# Sheet_4_2025-09-09.net
KiCad netlist of a schematic drawn in Altium Designer
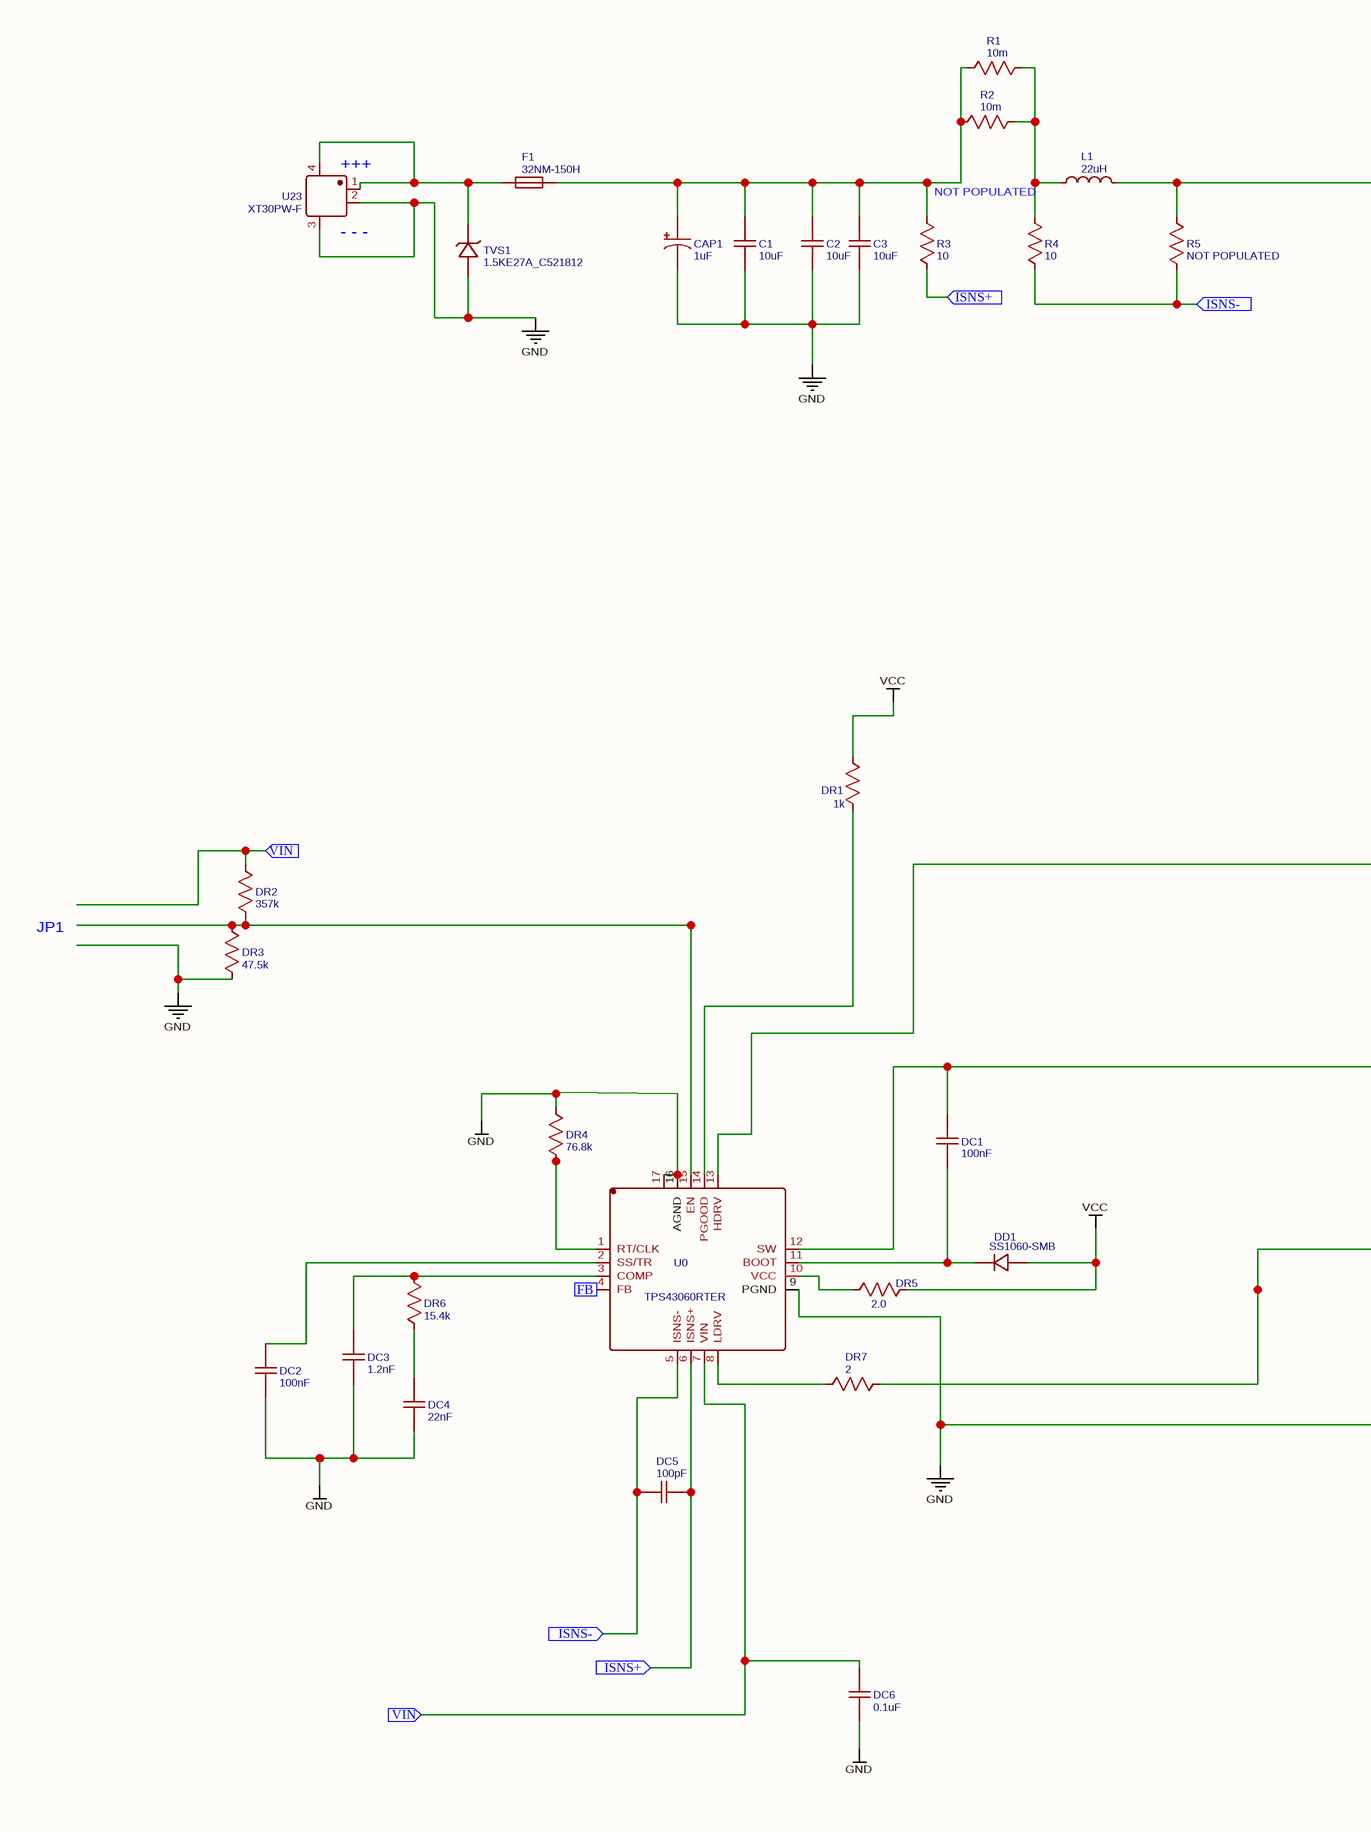
[diagram p0: Sheet_4_2025-09-09.schdoc, left]
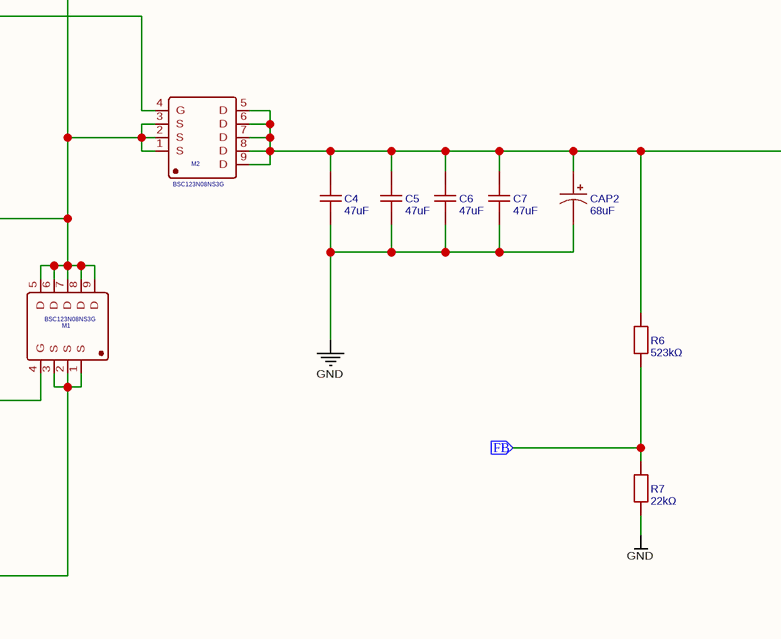
[diagram p1: Sheet_4_2025-09-09.schdoc, middle]
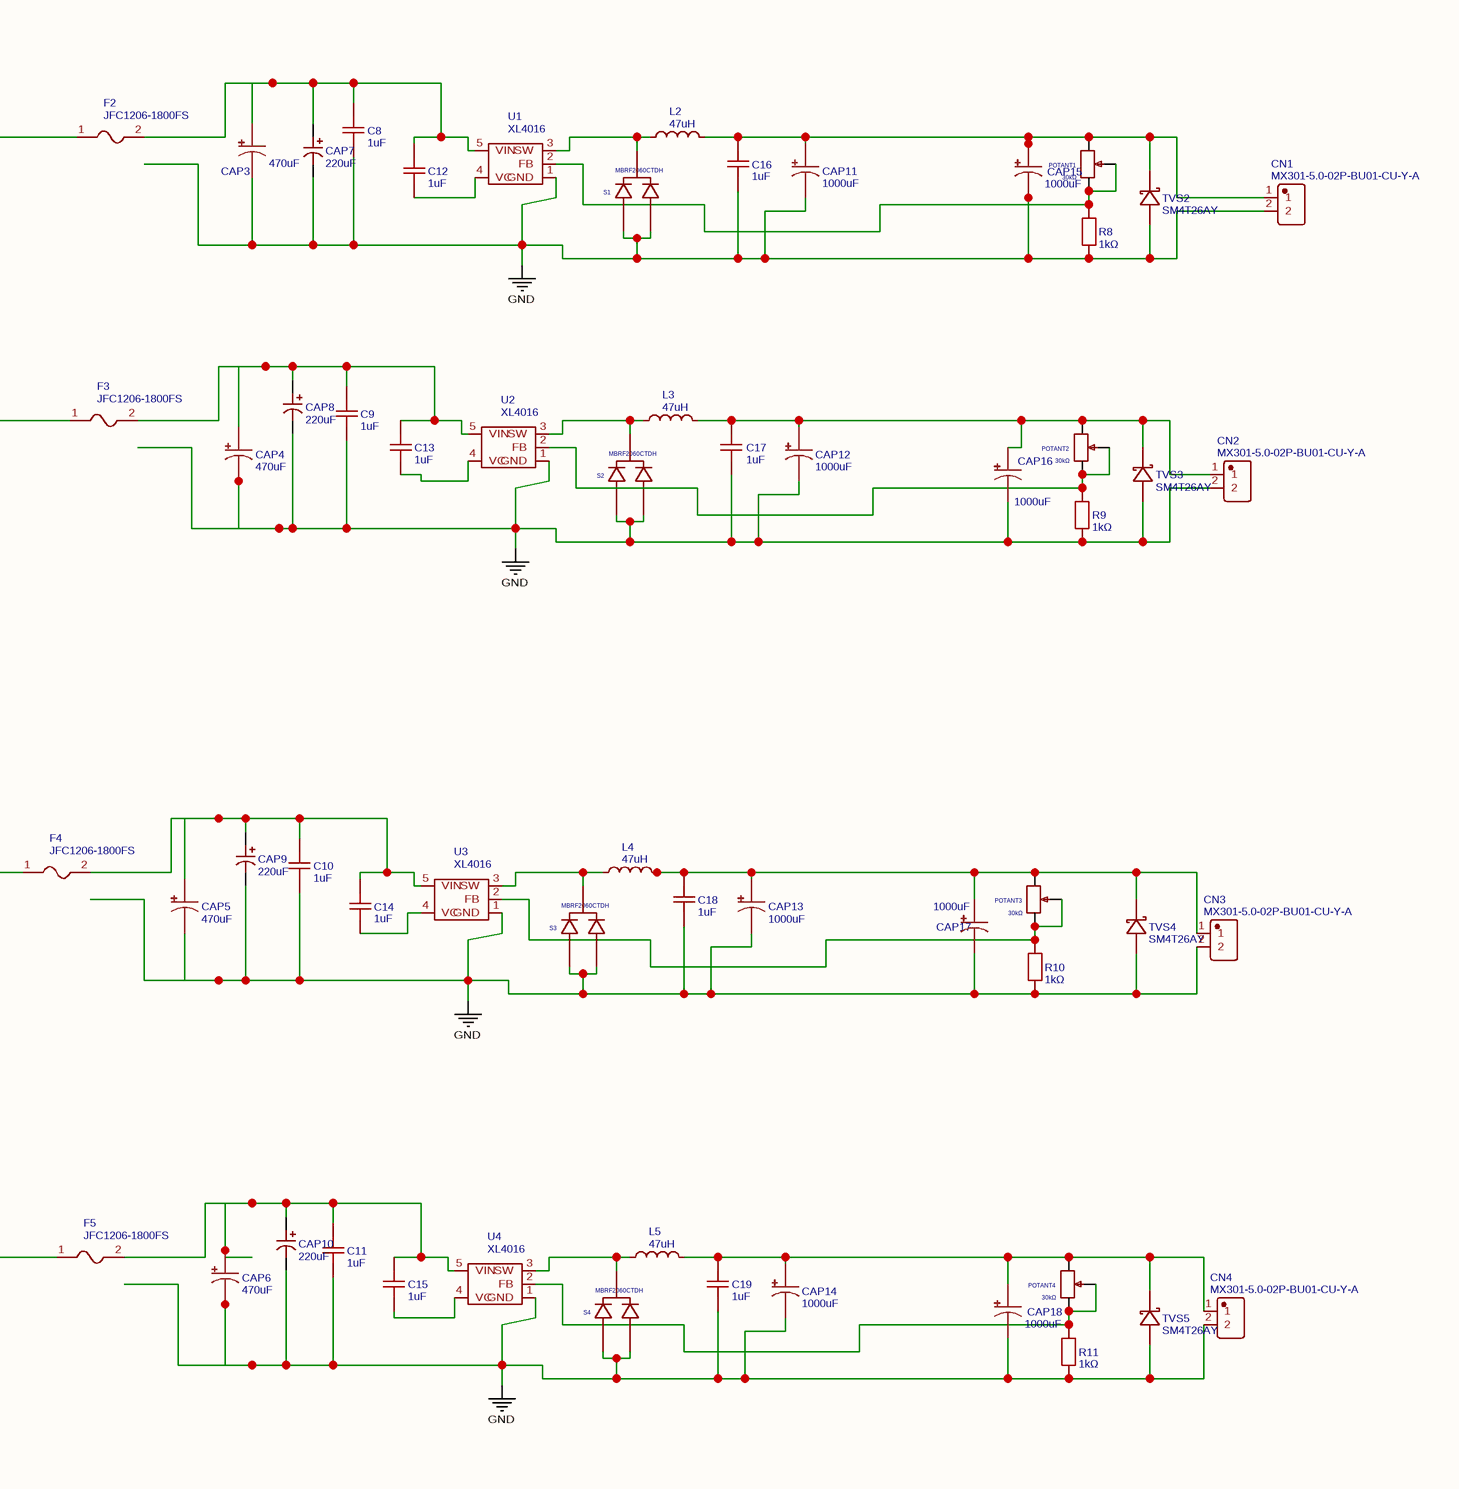
[diagram p2: Sheet_4_2025-09-09.schdoc, right]

(export (version "E")
  (design (tool "Eeschema 10.0.6"))
  (components
    (comp (ref "C1")
      (value "10uF")
      (fields
        (field (name "MANUFACTURER") "TDK")
        (field (name "MANUFACTURER PART") "CNC6P1X7R1H106K250AE")
        (field (name "CONTRIBUTOR") "lcsc")
      )
      (libsource (lib "altium-import") (part "root_3_10uF_"))
    )
    (comp (ref "C2")
      (value "10uF")
      (fields
        (field (name "MANUFACTURER") "TDK")
        (field (name "MANUFACTURER PART") "CNC6P1X7R1H106K250AE")
        (field (name "CONTRIBUTOR") "lcsc")
      )
      (libsource (lib "altium-import") (part "root_3_10uF_"))
    )
    (comp (ref "C3")
      (value "10uF")
      (fields
        (field (name "MANUFACTURER") "TDK")
        (field (name "MANUFACTURER PART") "CNC6P1X7R1H106K250AE")
        (field (name "CONTRIBUTOR") "lcsc")
      )
      (libsource (lib "altium-import") (part "root_3_10uF_"))
    )
    (comp (ref "C4")
      (value "47uF")
      (fields (field (name "CONTRIBUTOR") "LCEDA_Lib"))
      (libsource (lib "altium-import") (part "root_1_47uF_"))
    )
    (comp (ref "C5")
      (value "47uF")
      (fields (field (name "CONTRIBUTOR") "LCEDA_Lib"))
      (libsource (lib "altium-import") (part "root_1_47uF_"))
    )
    (comp (ref "C6")
      (value "47uF")
      (fields (field (name "CONTRIBUTOR") "LCEDA_Lib"))
      (libsource (lib "altium-import") (part "root_1_47uF_"))
    )
    (comp (ref "C7")
      (value "47uF")
      (fields (field (name "CONTRIBUTOR") "LCEDA_Lib"))
      (libsource (lib "altium-import") (part "root_1_47uF_"))
    )
    (comp (ref "C8")
      (value "1uF")
      (fields
        (field (name "MANUFACTURER") "TDK")
        (field (name "MANUFACTURER PART") "FK26X7R1H105KRE06")
        (field (name "CONTRIBUTOR") "LCSC")
      )
      (libsource (lib "altium-import") (part "root_3_1uF_"))
    )
    (comp (ref "C9")
      (value "1uF")
      (fields
        (field (name "MANUFACTURER") "TDK")
        (field (name "MANUFACTURER PART") "FK26X7R1H105KRE06")
        (field (name "CONTRIBUTOR") "LCSC")
      )
      (libsource (lib "altium-import") (part "root_3_1uF_"))
    )
    (comp (ref "C10")
      (value "1uF")
      (fields
        (field (name "MANUFACTURER") "TDK")
        (field (name "MANUFACTURER PART") "FK26X7R1H105KRE06")
        (field (name "CONTRIBUTOR") "LCSC")
      )
      (libsource (lib "altium-import") (part "root_3_1uF_"))
    )
    (comp (ref "C11")
      (value "1uF")
      (fields
        (field (name "MANUFACTURER") "TDK")
        (field (name "MANUFACTURER PART") "FK26X7R1H105KRE06")
        (field (name "CONTRIBUTOR") "LCSC")
      )
      (libsource (lib "altium-import") (part "root_3_1uF_"))
    )
    (comp (ref "C12")
      (value "1uF")
      (fields
        (field (name "MANUFACTURER") "TDK")
        (field (name "MANUFACTURER PART") "C1005X6S1A105K050BC")
        (field (name "CONTRIBUTOR") "lcsc")
      )
      (libsource (lib "") (part "root_3_1uF__1"))
    )
    (comp (ref "C13")
      (value "1uF")
      (fields
        (field (name "MANUFACTURER") "TDK")
        (field (name "MANUFACTURER PART") "C1005X6S1A105K050BC")
        (field (name "CONTRIBUTOR") "lcsc")
      )
      (libsource (lib "") (part "root_3_1uF__1"))
    )
    (comp (ref "C14")
      (value "1uF")
      (fields
        (field (name "MANUFACTURER") "TDK")
        (field (name "MANUFACTURER PART") "C1005X6S1A105K050BC")
        (field (name "CONTRIBUTOR") "lcsc")
      )
      (libsource (lib "") (part "root_3_1uF__1"))
    )
    (comp (ref "C15")
      (value "1uF")
      (fields
        (field (name "MANUFACTURER") "TDK")
        (field (name "MANUFACTURER PART") "C1005X6S1A105K050BC")
        (field (name "CONTRIBUTOR") "lcsc")
      )
      (libsource (lib "altium-import") (part "root_1_1uF_"))
    )
    (comp (ref "C16")
      (value "1uF")
      (fields
        (field (name "MANUFACTURER") "TDK")
        (field (name "MANUFACTURER PART") "FK26X7R1H105KRE06")
        (field (name "CONTRIBUTOR") "LCSC")
      )
      (libsource (lib "altium-import") (part "root_3_1uF_"))
    )
    (comp (ref "C17")
      (value "1uF")
      (fields
        (field (name "MANUFACTURER") "TDK")
        (field (name "MANUFACTURER PART") "FK26X7R1H105KRE06")
        (field (name "CONTRIBUTOR") "LCSC")
      )
      (libsource (lib "") (part "root_3_1uF__2"))
    )
    (comp (ref "C18")
      (value "1uF")
      (fields
        (field (name "MANUFACTURER") "TDK")
        (field (name "MANUFACTURER PART") "FK26X7R1H105KRE06")
        (field (name "CONTRIBUTOR") "LCSC")
      )
      (libsource (lib "altium-import") (part "root_3_1uF_"))
    )
    (comp (ref "C19")
      (value "1uF")
      (fields
        (field (name "MANUFACTURER") "TDK")
        (field (name "MANUFACTURER PART") "FK26X7R1H105KRE06")
        (field (name "CONTRIBUTOR") "LCSC")
      )
      (libsource (lib "altium-import") (part "root_3_1uF_"))
    )
    (comp (ref "CAP1")
      (value "1uF")
      (fields (field (name "MANUFACTURER") "HONOR(荣誉)") (field (name "MANUFACTURER PART") "HT2A1R0M0405"))
      (libsource (lib "altium-import") (part "root_0_1uF_"))
    )
    (comp (ref "CAP2")
      (value "68uF")
      (fields (field (name "CONTRIBUTOR") "LCEDA_Lib"))
      (libsource (lib "altium-import") (part "root_3_68uF_"))
    )
    (comp (ref "CAP3")
      (value "470uF")
      (fields
        (field (name "MANUFACTURER") "BERYL(绿宝石)")
        (field (name "MANUFACTURER PART") "RC063M471LO13*20TH-2A1E")
        (field (name "CONTRIBUTOR") "LCSC")
      )
      (libsource (lib "altium-import") (part "root_0_470uF_"))
    )
    (comp (ref "CAP4")
      (value "470uF")
      (fields
        (field (name "MANUFACTURER") "BERYL(绿宝石)")
        (field (name "MANUFACTURER PART") "RC063M471LO13*20TH-2A1E")
        (field (name "CONTRIBUTOR") "LCSC")
      )
      (libsource (lib "altium-import") (part "root_0_470uF_"))
    )
    (comp (ref "CAP5")
      (value "470uF")
      (fields
        (field (name "MANUFACTURER") "BERYL(绿宝石)")
        (field (name "MANUFACTURER PART") "RC063M471LO13*20TH-2A1E")
        (field (name "CONTRIBUTOR") "LCSC")
      )
      (libsource (lib "altium-import") (part "root_0_470uF_"))
    )
    (comp (ref "CAP6")
      (value "470uF")
      (fields
        (field (name "MANUFACTURER") "BERYL(绿宝石)")
        (field (name "MANUFACTURER PART") "RC063M471LO13*20TH-2A1E")
        (field (name "CONTRIBUTOR") "LCSC")
      )
      (libsource (lib "altium-import") (part "root_0_470uF_"))
    )
    (comp (ref "CAP7")
      (value "220uF")
      (fields
        (field (name "MANUFACTURER") "KNSCHA(科尼盛)")
        (field (name "MANUFACTURER PART") "189RV0038")
        (field (name "CONTRIBUTOR") "lcsc")
      )
      (libsource (lib "altium-import") (part "root_3_220uF_"))
    )
    (comp (ref "CAP8")
      (value "220uF")
      (fields
        (field (name "MANUFACTURER") "KNSCHA(科尼盛)")
        (field (name "MANUFACTURER PART") "189RV0038")
        (field (name "CONTRIBUTOR") "lcsc")
      )
      (libsource (lib "altium-import") (part "root_3_220uF_"))
    )
    (comp (ref "CAP9")
      (value "220uF")
      (fields
        (field (name "MANUFACTURER") "KNSCHA(科尼盛)")
        (field (name "MANUFACTURER PART") "189RV0038")
        (field (name "CONTRIBUTOR") "lcsc")
      )
      (libsource (lib "altium-import") (part "root_3_220uF_"))
    )
    (comp (ref "CAP10")
      (value "220uF")
      (fields
        (field (name "MANUFACTURER") "KNSCHA(科尼盛)")
        (field (name "MANUFACTURER PART") "189RV0038")
        (field (name "CONTRIBUTOR") "lcsc")
      )
      (libsource (lib "altium-import") (part "root_3_220uF_"))
    )
    (comp (ref "CAP11")
      (value "1000uF")
      (fields
        (field (name "MANUFACTURER") "Ymin(永铭)")
        (field (name "MANUFACTURER PART") "PKCL2001H102MF")
        (field (name "CONTRIBUTOR") "LCSC")
      )
      (libsource (lib "altium-import") (part "root_0_1000uF_"))
    )
    (comp (ref "CAP12")
      (value "1000uF")
      (fields
        (field (name "MANUFACTURER") "Ymin(永铭)")
        (field (name "MANUFACTURER PART") "PKCL2001H102MF")
        (field (name "CONTRIBUTOR") "LCSC")
      )
      (libsource (lib "altium-import") (part "root_0_1000uF_"))
    )
    (comp (ref "CAP13")
      (value "1000uF")
      (fields
        (field (name "MANUFACTURER") "Ymin(永铭)")
        (field (name "MANUFACTURER PART") "PKCL2001H102MF")
        (field (name "CONTRIBUTOR") "LCSC")
      )
      (libsource (lib "altium-import") (part "root_0_1000uF_"))
    )
    (comp (ref "CAP14")
      (value "1000uF")
      (fields
        (field (name "MANUFACTURER") "Ymin(永铭)")
        (field (name "MANUFACTURER PART") "PKCL2001H102MF")
        (field (name "CONTRIBUTOR") "LCSC")
      )
      (libsource (lib "altium-import") (part "root_0_1000uF_"))
    )
    (comp (ref "CAP15")
      (value "1000uF")
      (fields
        (field (name "MANUFACTURER") "Ymin(永铭)")
        (field (name "MANUFACTURER PART") "LKML3001J102MF")
        (field (name "CONTRIBUTOR") "LCSC")
      )
      (libsource (lib "altium-import") (part "root_0_1000uF_"))
    )
    (comp (ref "CAP16")
      (value "1000uF")
      (fields
        (field (name "MANUFACTURER") "Ymin(永铭)")
        (field (name "MANUFACTURER PART") "LKML3001J102MF")
        (field (name "CONTRIBUTOR") "LCSC")
      )
      (libsource (lib "altium-import") (part "root_0_1000uF_"))
    )
    (comp (ref "CAP17")
      (value "1000uF")
      (fields
        (field (name "MANUFACTURER") "Ymin(永铭)")
        (field (name "MANUFACTURER PART") "LKML3001J102MF")
        (field (name "CONTRIBUTOR") "LCSC")
      )
      (libsource (lib "altium-import") (part "root_0_1000uF_"))
    )
    (comp (ref "CAP18")
      (value "1000uF")
      (fields
        (field (name "MANUFACTURER") "Ymin(永铭)")
        (field (name "MANUFACTURER PART") "LKML3001J102MF")
        (field (name "CONTRIBUTOR") "LCSC")
      )
      (libsource (lib "altium-import") (part "root_0_1000uF_"))
    )
    (comp (ref "CN1")
      (value "MX301-5.0-02P-BU01-CU-Y-A")
      (fields
        (field (name "MANUFACTURER") "MAX(迈旭)")
        (field (name "MANUFACTURER PART") "MX301-5.0-02P-BU01-Cu-Y-A")
        (field (name "CONTRIBUTOR") "lcsc")
      )
      (libsource (lib "altium-import") (part "root_0_MX301-5.0-02P-BU01-CU-Y-A_"))
    )
    (comp (ref "CN2")
      (value "MX301-5.0-02P-BU01-CU-Y-A")
      (fields
        (field (name "MANUFACTURER") "MAX(迈旭)")
        (field (name "MANUFACTURER PART") "MX301-5.0-02P-BU01-Cu-Y-A")
        (field (name "CONTRIBUTOR") "lcsc")
      )
      (libsource (lib "altium-import") (part "root_0_MX301-5.0-02P-BU01-CU-Y-A_"))
    )
    (comp (ref "CN3")
      (value "MX301-5.0-02P-BU01-CU-Y-A")
      (fields
        (field (name "MANUFACTURER") "MAX(迈旭)")
        (field (name "MANUFACTURER PART") "MX301-5.0-02P-BU01-Cu-Y-A")
        (field (name "CONTRIBUTOR") "lcsc")
      )
      (libsource (lib "altium-import") (part "root_0_MX301-5.0-02P-BU01-CU-Y-A_"))
    )
    (comp (ref "CN4")
      (value "MX301-5.0-02P-BU01-CU-Y-A")
      (fields
        (field (name "MANUFACTURER") "MAX(迈旭)")
        (field (name "MANUFACTURER PART") "MX301-5.0-02P-BU01-Cu-Y-A")
        (field (name "CONTRIBUTOR") "lcsc")
      )
      (libsource (lib "altium-import") (part "root_0_MX301-5.0-02P-BU01-CU-Y-A_"))
    )
    (comp (ref "DC1")
      (value "100nF")
      (fields
        (field (name "MANUFACTURER") "SHM(南方宏明)")
        (field (name "MANUFACTURER PART") "DCS104M26Y5UH6FJ5A0")
        (field (name "CONTRIBUTOR") "lcsc")
      )
      (libsource (lib "altium-import") (part "root_3_100nF_"))
    )
    (comp (ref "DC2")
      (value "100nF")
      (fields
        (field (name "MANUFACTURER") "SHM(南方宏明)")
        (field (name "MANUFACTURER PART") "DCS104M26Y5UH6FJ5A0")
        (field (name "CONTRIBUTOR") "lcsc")
      )
      (libsource (lib "altium-import") (part "root_1_100nF_"))
    )
    (comp (ref "DC3")
      (value "1.2nF")
      (fields
        (field (name "MANUFACTURER") "KYET(科雅)")
        (field (name "MANUFACTURER PART") "PE122J2A0501")
        (field (name "CONTRIBUTOR") "LCSC")
      )
      (libsource (lib "altium-import") (part "root_1_1.2nF_"))
    )
    (comp (ref "DC4")
      (value "22nF")
      (fields
        (field (name "MANUFACTURER") "SHM(南方宏明)")
        (field (name "MANUFACTURER PART") "DCM223M39Y5VL6FJ5A0")
        (field (name "CONTRIBUTOR") "LCSC")
      )
      (libsource (lib "altium-import") (part "root_1_22nF_"))
    )
    (comp (ref "DC5")
      (value "100pF")
      (fields
        (field (name "MANUFACTURER") "SHM(南方宏明)")
        (field (name "MANUFACTURER PART") "DCC101J26COHF6FJ5A0")
        (field (name "CONTRIBUTOR") "lcsc")
      )
      (libsource (lib "altium-import") (part "root_0_100pF_"))
    )
    (comp (ref "DC6")
      (value "0.1uF")
      (fields (field (name "CONTRIBUTOR") "LCEDA_Lib"))
      (libsource (lib "altium-import") (part "root_1_0.1uF_"))
    )
    (comp (ref "DD1")
      (value "SS1060-SMB")
      (fields (field (name "MANUFACTURER") "GOODWORK(固得沃克)") (field (name "CONTRIBUTOR") "lcsc"))
      (libsource (lib "altium-import") (part "root_0_SS1060-SMB_"))
    )
    (comp (ref "DR1")
      (value "1k")
      (fields (field (name "CONTRIBUTOR") "LCEDA_Lib"))
      (libsource (lib "altium-import") (part "root_1_1k_"))
    )
    (comp (ref "DR2")
      (value "357k")
      (fields (field (name "CONTRIBUTOR") "LCEDA_Lib"))
      (libsource (lib "altium-import") (part "root_1_357k_"))
    )
    (comp (ref "DR3")
      (value "47.5k")
      (fields (field (name "CONTRIBUTOR") "LCEDA_Lib"))
      (libsource (lib "altium-import") (part "root_1_47.5k_"))
    )
    (comp (ref "DR4")
      (value "76.8k")
      (fields (field (name "CONTRIBUTOR") "LCEDA_Lib"))
      (libsource (lib "altium-import") (part "root_1_76.8k_"))
    )
    (comp (ref "DR5")
      (value "2.0")
      (fields (field (name "CONTRIBUTOR") "LCEDA_Lib"))
      (libsource (lib "altium-import") (part "root_0_2.0_"))
    )
    (comp (ref "DR6")
      (value "15.4k")
      (fields (field (name "CONTRIBUTOR") "LCEDA_Lib"))
      (libsource (lib "altium-import") (part "root_1_15.4k_"))
    )
    (comp (ref "DR7")
      (value "2")
      (fields (field (name "CONTRIBUTOR") "LCEDA_Lib"))
      (libsource (lib "altium-import") (part "root_0_2_"))
    )
    (comp (ref "F1")
      (value "32NM-150H")
      (fields (field (name "MANUFACTURER") "HOLLY(好利来)") (field (name "CONTRIBUTOR") "LCSC"))
      (libsource (lib "altium-import") (part "root_0_32NM-150H_"))
    )
    (comp (ref "F2")
      (value "JFC1206-1800FS")
      (fields (field (name "MANUFACTURER") "JDTfuse(集电通)") (field (name "CONTRIBUTOR") "LCSC"))
      (libsource (lib "altium-import") (part "root_0_JFC1206-1800FS_"))
    )
    (comp (ref "F3")
      (value "JFC1206-1800FS")
      (fields (field (name "MANUFACTURER") "JDTfuse(集电通)") (field (name "CONTRIBUTOR") "LCSC"))
      (libsource (lib "altium-import") (part "root_0_JFC1206-1800FS_"))
    )
    (comp (ref "F4")
      (value "JFC1206-1800FS")
      (fields (field (name "MANUFACTURER") "JDTfuse(集电通)") (field (name "CONTRIBUTOR") "LCSC"))
      (libsource (lib "altium-import") (part "root_0_JFC1206-1800FS_"))
    )
    (comp (ref "F5")
      (value "JFC1206-1800FS")
      (fields (field (name "MANUFACTURER") "JDTfuse(集电通)") (field (name "CONTRIBUTOR") "LCSC"))
      (libsource (lib "altium-import") (part "root_0_JFC1206-1800FS_"))
    )
    (comp (ref "L1")
      (value "22uH")
      (fields
        (field (name "MANUFACTURER") "PROD(谱罗德)")
        (field (name "MANUFACTURER PART") "PDMTAT068125-220MLU")
        (field (name "CONTRIBUTOR") "lcsc")
      )
      (libsource (lib "altium-import") (part "root_0_22uH_"))
    )
    (comp (ref "L2")
      (value "47uH")
      (fields
        (field (name "MANUFACTURER") "PROD(谱罗德)")
        (field (name "MANUFACTURER PART") "PDPMAA1712-470MP")
        (field (name "CONTRIBUTOR") "lcsc")
      )
      (libsource (lib "altium-import") (part "root_0_47uH_"))
    )
    (comp (ref "L3")
      (value "47uH")
      (fields
        (field (name "MANUFACTURER") "PROD(谱罗德)")
        (field (name "MANUFACTURER PART") "PDPMAA1712-470MP")
        (field (name "CONTRIBUTOR") "lcsc")
      )
      (libsource (lib "altium-import") (part "root_0_47uH_"))
    )
    (comp (ref "L4")
      (value "47uH")
      (fields
        (field (name "MANUFACTURER") "PROD(谱罗德)")
        (field (name "MANUFACTURER PART") "PDPMAA1712-470MP")
        (field (name "CONTRIBUTOR") "lcsc")
      )
      (libsource (lib "altium-import") (part "root_0_47uH_"))
    )
    (comp (ref "L5")
      (value "47uH")
      (fields
        (field (name "MANUFACTURER") "PROD(谱罗德)")
        (field (name "MANUFACTURER PART") "PDPMAA1712-470MP")
        (field (name "CONTRIBUTOR") "lcsc")
      )
      (libsource (lib "altium-import") (part "root_0_47uH_"))
    )
    (comp (ref "M1")
      (value "BSC123N08NS3G")
      (fields (field (name "MANUFACTURER") "Infineon(英飞凌)") (field (name "CONTRIBUTOR") "LCSC"))
      (libsource (lib "altium-import") (part "root_1_BSC123N08NS3G_"))
    )
    (comp (ref "M2")
      (value "BSC123N08NS3G")
      (fields (field (name "MANUFACTURER") "Infineon(英飞凌)") (field (name "CONTRIBUTOR") "LCSC"))
      (libsource (lib "altium-import") (part "root_0_BSC123N08NS3G_"))
    )
    (comp (ref "POTANT1")
      (value "30kΩ")
      (fields (field (name "MANUFACTURER") "BOURNS") (field (name "MANUFACTURER PART") "3362P-1-103LF"))
      (libsource (lib "altium-import") (part "root_0_30kΩ_"))
    )
    (comp (ref "POTANT2")
      (value "30kΩ")
      (fields (field (name "MANUFACTURER") "BOURNS") (field (name "MANUFACTURER PART") "3362P-1-103LF"))
      (libsource (lib "altium-import") (part "root_0_30kΩ_"))
    )
    (comp (ref "POTANT3")
      (value "30kΩ")
      (fields (field (name "MANUFACTURER") "BOURNS") (field (name "MANUFACTURER PART") "3362P-1-103LF"))
      (libsource (lib "altium-import") (part "root_0_30kΩ_"))
    )
    (comp (ref "POTANT4")
      (value "30kΩ")
      (fields (field (name "MANUFACTURER") "BOURNS") (field (name "MANUFACTURER PART") "3362P-1-103LF"))
      (libsource (lib "altium-import") (part "root_0_30kΩ_"))
    )
    (comp (ref "R1")
      (value "10m")
      (fields (field (name "CONTRIBUTOR") "LCEDA_Lib"))
      (libsource (lib "altium-import") (part "root_0_10m_"))
    )
    (comp (ref "R2")
      (value "10m")
      (fields (field (name "CONTRIBUTOR") "LCEDA_Lib"))
      (libsource (lib "altium-import") (part "root_0_10m_"))
    )
    (comp (ref "R3")
      (value "10")
      (fields (field (name "CONTRIBUTOR") "LCEDA_Lib"))
      (libsource (lib "altium-import") (part "root_1_10_"))
    )
    (comp (ref "R4")
      (value "10")
      (fields (field (name "CONTRIBUTOR") "LCEDA_Lib"))
      (libsource (lib "altium-import") (part "root_1_10_"))
    )
    (comp (ref "R5")
      (value "NOT POPULATED")
      (fields (field (name "CONTRIBUTOR") "LCEDA_Lib"))
      (libsource (lib "altium-import") (part "root_1_NOT POPULATED_"))
    )
    (comp (ref "R6")
      (value "523kΩ")
      (fields
        (field (name "MANUFACTURER") "YAGEO(国巨)")
        (field (name "MANUFACTURER PART") "MFR-25FBF52-523K")
        (field (name "CONTRIBUTOR") "lcsc")
      )
      (libsource (lib "altium-import") (part "root_1_523kΩ_"))
    )
    (comp (ref "R7")
      (value "22kΩ")
      (fields
        (field (name "MANUFACTURER") "Tyohm(幸亚电阻)")
        (field (name "MANUFACTURER PART") "RN 3WS 22K F T/B A1")
        (field (name "CONTRIBUTOR") "LCSC")
      )
      (libsource (lib "altium-import") (part "root_3_22kΩ_"))
    )
    (comp (ref "R8")
      (value "1kΩ")
      (fields
        (field (name "MANUFACTURER") "YAGEO(国巨)")
        (field (name "MANUFACTURER PART") "MF0207FTE52-1K")
        (field (name "CONTRIBUTOR") "lcsc")
      )
      (libsource (lib "altium-import") (part "root_3_1kΩ_"))
    )
    (comp (ref "R9")
      (value "1kΩ")
      (fields
        (field (name "MANUFACTURER") "YAGEO(国巨)")
        (field (name "MANUFACTURER PART") "MF0207FTE52-1K")
        (field (name "CONTRIBUTOR") "lcsc")
      )
      (libsource (lib "altium-import") (part "root_3_1kΩ_"))
    )
    (comp (ref "R10")
      (value "1kΩ")
      (fields
        (field (name "MANUFACTURER") "YAGEO(国巨)")
        (field (name "MANUFACTURER PART") "MF0207FTE52-1K")
        (field (name "CONTRIBUTOR") "lcsc")
      )
      (libsource (lib "altium-import") (part "root_3_1kΩ_"))
    )
    (comp (ref "R11")
      (value "1kΩ")
      (fields
        (field (name "MANUFACTURER") "YAGEO(国巨)")
        (field (name "MANUFACTURER PART") "MF0207FTE52-1K")
        (field (name "CONTRIBUTOR") "lcsc")
      )
      (libsource (lib "altium-import") (part "root_3_1kΩ_"))
    )
    (comp (ref "S1")
      (value "MBRF2060CTDH")
      (fields (field (name "MANUFACTURER") "迪一") (field (name "CONTRIBUTOR") "lcsc"))
      (libsource (lib "altium-import") (part "root_3_MBRF2060CTDH_"))
    )
    (comp (ref "S2")
      (value "MBRF2060CTDH")
      (fields (field (name "MANUFACTURER") "迪一") (field (name "CONTRIBUTOR") "lcsc"))
      (libsource (lib "altium-import") (part "root_3_MBRF2060CTDH_"))
    )
    (comp (ref "S3")
      (value "MBRF2060CTDH")
      (fields (field (name "MANUFACTURER") "迪一") (field (name "CONTRIBUTOR") "lcsc"))
      (libsource (lib "altium-import") (part "root_3_MBRF2060CTDH_"))
    )
    (comp (ref "S4")
      (value "MBRF2060CTDH")
      (fields (field (name "MANUFACTURER") "迪一") (field (name "CONTRIBUTOR") "lcsc"))
      (libsource (lib "altium-import") (part "root_3_MBRF2060CTDH_"))
    )
    (comp (ref "TVS1")
      (value "1.5KE27A_C521812")
      (fields
        (field (name "MANUFACTURER") "Brightking(君耀电子)")
        (field (name "MANUFACTURER PART") "1.5KE27A/B")
        (field (name "CONTRIBUTOR") "LCSC")
      )
      (libsource (lib "altium-import") (part "root_3_1.5KE27A_C521812_"))
    )
    (comp (ref "TVS2")
      (value "SM4T26AY")
      (fields (field (name "MANUFACTURER") "ST(意法半导体)") (field (name "CONTRIBUTOR") "LCSC"))
      (libsource (lib "altium-import") (part "root_3_SM4T26AY_"))
    )
    (comp (ref "TVS3")
      (value "SM4T26AY")
      (fields (field (name "MANUFACTURER") "ST(意法半导体)") (field (name "CONTRIBUTOR") "LCSC"))
      (libsource (lib "altium-import") (part "root_3_SM4T26AY_"))
    )
    (comp (ref "TVS4")
      (value "SM4T26AY")
      (fields (field (name "MANUFACTURER") "ST(意法半导体)") (field (name "CONTRIBUTOR") "LCSC"))
      (libsource (lib "altium-import") (part "root_3_SM4T26AY_"))
    )
    (comp (ref "TVS5")
      (value "SM4T26AY")
      (fields (field (name "MANUFACTURER") "ST(意法半导体)") (field (name "CONTRIBUTOR") "LCSC"))
      (libsource (lib "altium-import") (part "root_3_SM4T26AY_"))
    )
    (comp (ref "U0")
      (value "TPS43060RTER")
      (fields (field (name "MANUFACTURER") "TI(德州仪器)") (field (name "CONTRIBUTOR") "LCSC"))
      (libsource (lib "altium-import") (part "root_0_TPS43060RTER_"))
    )
    (comp (ref "U1")
      (value "XL4016")
      (fields
        (field (name "MANUFACTURER PART") "XL4016E1")
        (field (name "MANUFACTURER") "XLSEMI")
        (field (name "CONTRIBUTOR") "andyfierman")
      )
      (libsource (lib "altium-import") (part "root_0_XL4016_"))
    )
    (comp (ref "U2")
      (value "XL4016")
      (fields
        (field (name "MANUFACTURER PART") "XL4016E1")
        (field (name "MANUFACTURER") "XLSEMI")
        (field (name "CONTRIBUTOR") "andyfierman")
      )
      (libsource (lib "altium-import") (part "root_0_XL4016_"))
    )
    (comp (ref "U3")
      (value "XL4016")
      (fields
        (field (name "MANUFACTURER PART") "XL4016E1")
        (field (name "MANUFACTURER") "XLSEMI")
        (field (name "CONTRIBUTOR") "andyfierman")
      )
      (libsource (lib "altium-import") (part "root_0_XL4016_"))
    )
    (comp (ref "U4")
      (value "XL4016")
      (fields
        (field (name "MANUFACTURER PART") "XL4016E1")
        (field (name "MANUFACTURER") "XLSEMI")
        (field (name "CONTRIBUTOR") "andyfierman")
      )
      (libsource (lib "altium-import") (part "root_0_XL4016_"))
    )
    (comp (ref "U23")
      (value "XT30PW-F")
      (fields (field (name "CONTRIBUTOR") "LCSC"))
      (libsource (lib "altium-import") (part "root_0_XT30PW-F_"))
    )
  )
  (nets
    (net (code "1") (name "/FB") (class "Default")
      (node (ref "R6") (pin "1") (pinfunction "1_1") (pintype "passive"))
      (node (ref "R7") (pin "1") (pinfunction "1_1") (pintype "passive"))
      (node (ref "U0") (pin "4") (pinfunction "FB_4") (pintype "passive"))
    )
    (net (code "2") (name "/ISNS+") (class "Default")
      (node (ref "DC5") (pin "2") (pinfunction "2_2") (pintype "passive"))
      (node (ref "R3") (pin "1") (pinfunction "1_1") (pintype "passive"))
      (node (ref "U0") (pin "6") (pinfunction "ISNS+_6") (pintype "passive"))
    )
    (net (code "3") (name "/ISNS-") (class "Default")
      (node (ref "DC5") (pin "1") (pinfunction "1_1") (pintype "passive"))
      (node (ref "R4") (pin "1") (pinfunction "1_1") (pintype "passive"))
      (node (ref "R5") (pin "1") (pinfunction "1_1") (pintype "passive"))
      (node (ref "U0") (pin "5") (pinfunction "ISNS-_5") (pintype "passive"))
    )
    (net (code "4") (name "/VIN") (class "Default")
      (node (ref "DC6") (pin "2") (pinfunction "2_2") (pintype "passive"))
      (node (ref "DR2") (pin "2") (pinfunction "2_2") (pintype "passive"))
      (node (ref "U0") (pin "7") (pinfunction "VIN_7") (pintype "passive"))
    )
    (net (code "5") (name "GND") (class "Default")
      (node (ref "C1") (pin "1") (pinfunction "1_1") (pintype "passive"))
      (node (ref "C10") (pin "2") (pinfunction "2_2") (pintype "passive"))
      (node (ref "C11") (pin "2") (pinfunction "2_2") (pintype "passive"))
      (node (ref "C16") (pin "2") (pinfunction "2_2") (pintype "passive"))
      (node (ref "C17") (pin "1") (pinfunction "1_1") (pintype "passive"))
      (node (ref "C18") (pin "2") (pinfunction "2_2") (pintype "passive"))
      (node (ref "C19") (pin "2") (pinfunction "2_2") (pintype "passive"))
      (node (ref "C2") (pin "1") (pinfunction "1_1") (pintype "passive"))
      (node (ref "C3") (pin "1") (pinfunction "1_1") (pintype "passive"))
      (node (ref "C4") (pin "1") (pinfunction "1_1") (pintype "passive"))
      (node (ref "C5") (pin "1") (pinfunction "1_1") (pintype "passive"))
      (node (ref "C6") (pin "1") (pinfunction "1_1") (pintype "passive"))
      (node (ref "C7") (pin "1") (pinfunction "1_1") (pintype "passive"))
      (node (ref "C8") (pin "2") (pinfunction "2_2") (pintype "passive"))
      (node (ref "C9") (pin "2") (pinfunction "2_2") (pintype "passive"))
      (node (ref "CAP1") (pin "2") (pinfunction "2_2") (pintype "passive"))
      (node (ref "CAP10") (pin "2") (pinfunction "2_2") (pintype "passive"))
      (node (ref "CAP11") (pin "2") (pinfunction "2_2") (pintype "passive"))
      (node (ref "CAP12") (pin "2") (pinfunction "2_2") (pintype "passive"))
      (node (ref "CAP13") (pin "2") (pinfunction "2_2") (pintype "passive"))
      (node (ref "CAP14") (pin "2") (pinfunction "2_2") (pintype "passive"))
      (node (ref "CAP15") (pin "2") (pinfunction "2_2") (pintype "passive"))
      (node (ref "CAP16") (pin "2") (pinfunction "2_2") (pintype "passive"))
      (node (ref "CAP17") (pin "2") (pinfunction "2_2") (pintype "passive"))
      (node (ref "CAP18") (pin "2") (pinfunction "2_2") (pintype "passive"))
      (node (ref "CAP2") (pin "2") (pinfunction "2_2") (pintype "passive"))
      (node (ref "CAP3") (pin "2") (pinfunction "2_2") (pintype "passive"))
      (node (ref "CAP4") (pin "2") (pinfunction "2_2") (pintype "passive"))
      (node (ref "CAP5") (pin "2") (pinfunction "2_2") (pintype "passive"))
      (node (ref "CAP6") (pin "2") (pinfunction "2_2") (pintype "passive"))
      (node (ref "CAP7") (pin "2") (pinfunction "2_2") (pintype "passive"))
      (node (ref "CAP8") (pin "2") (pinfunction "2_2") (pintype "passive"))
      (node (ref "CAP9") (pin "2") (pinfunction "2_2") (pintype "passive"))
      (node (ref "CN1") (pin "2") (pinfunction "2_2") (pintype "passive"))
      (node (ref "CN2") (pin "2") (pinfunction "2_2") (pintype "passive"))
      (node (ref "CN3") (pin "2") (pinfunction "2_2") (pintype "passive"))
      (node (ref "CN4") (pin "2") (pinfunction "2_2") (pintype "passive"))
      (node (ref "DC2") (pin "1") (pinfunction "1_1") (pintype "passive"))
      (node (ref "DC3") (pin "1") (pinfunction "1_1") (pintype "passive"))
      (node (ref "DC4") (pin "1") (pinfunction "1_1") (pintype "passive"))
      (node (ref "DC6") (pin "1") (pinfunction "1_1") (pintype "passive"))
      (node (ref "DR3") (pin "1") (pinfunction "1_1") (pintype "passive"))
      (node (ref "DR4") (pin "2") (pinfunction "2_2") (pintype "passive"))
      (node (ref "M1") (pin "1") (pinfunction "S_1") (pintype "passive"))
      (node (ref "M1") (pin "2") (pinfunction "S_2") (pintype "passive"))
      (node (ref "M1") (pin "3") (pinfunction "S_3") (pintype "passive"))
      (node (ref "R10") (pin "2") (pinfunction "2_2") (pintype "passive"))
      (node (ref "R11") (pin "2") (pinfunction "2_2") (pintype "passive"))
      (node (ref "R7") (pin "2") (pinfunction "2_2") (pintype "passive"))
      (node (ref "R8") (pin "2") (pinfunction "2_2") (pintype "passive"))
      (node (ref "R9") (pin "2") (pinfunction "2_2") (pintype "passive"))
      (node (ref "S1") (pin "1") (pinfunction "1_1") (pintype "passive"))
      (node (ref "S1") (pin "3") (pinfunction "3_3") (pintype "passive"))
      (node (ref "S2") (pin "1") (pinfunction "1_1") (pintype "passive"))
      (node (ref "S2") (pin "3") (pinfunction "3_3") (pintype "passive"))
      (node (ref "S3") (pin "1") (pinfunction "1_1") (pintype "passive"))
      (node (ref "S3") (pin "3") (pinfunction "3_3") (pintype "passive"))
      (node (ref "S4") (pin "1") (pinfunction "1_1") (pintype "passive"))
      (node (ref "S4") (pin "3") (pinfunction "3_3") (pintype "passive"))
      (node (ref "TVS1") (pin "2") (pinfunction "A_2") (pintype "passive"))
      (node (ref "TVS2") (pin "2") (pinfunction "2_2") (pintype "passive"))
      (node (ref "TVS3") (pin "2") (pinfunction "2_2") (pintype "passive"))
      (node (ref "TVS4") (pin "2") (pinfunction "2_2") (pintype "passive"))
      (node (ref "TVS5") (pin "2") (pinfunction "2_2") (pintype "passive"))
      (node (ref "U0") (pin "16") (pinfunction "AGND_16") (pintype "passive"))
      (node (ref "U0") (pin "17") (pinfunction "PAD_17") (pintype "passive"))
      (node (ref "U0") (pin "9") (pinfunction "PGND_9") (pintype "passive"))
      (node (ref "U1") (pin "1") (pinfunction "GND_1") (pintype "passive"))
      (node (ref "U2") (pin "1") (pinfunction "GND_1") (pintype "passive"))
      (node (ref "U23") (pin "2") (pinfunction "2_2") (pintype "passive"))
      (node (ref "U23") (pin "3") (pinfunction "3_3") (pintype "passive"))
      (node (ref "U3") (pin "1") (pinfunction "GND_1") (pintype "passive"))
      (node (ref "U4") (pin "1") (pinfunction "GND_1") (pintype "passive"))
    )
    (net (code "6") (name "Net-(C1-Pad2)") (class "Default")
      (node (ref "C1") (pin "2") (pinfunction "2_2") (pintype "passive"))
      (node (ref "C2") (pin "2") (pinfunction "2_2") (pintype "passive"))
      (node (ref "C3") (pin "2") (pinfunction "2_2") (pintype "passive"))
      (node (ref "CAP1") (pin "1") (pinfunction "1_1") (pintype "passive"))
      (node (ref "F1") (pin "2") (pinfunction "2_2") (pintype "passive"))
      (node (ref "R1") (pin "1") (pinfunction "1_1") (pintype "passive"))
      (node (ref "R2") (pin "1") (pinfunction "1_1") (pintype "passive"))
      (node (ref "R3") (pin "2") (pinfunction "2_2") (pintype "passive"))
    )
    (net (code "7") (name "Net-(C4-Pad2)") (class "Default")
      (node (ref "C4") (pin "2") (pinfunction "2_2") (pintype "passive"))
      (node (ref "C5") (pin "2") (pinfunction "2_2") (pintype "passive"))
      (node (ref "C6") (pin "2") (pinfunction "2_2") (pintype "passive"))
      (node (ref "C7") (pin "2") (pinfunction "2_2") (pintype "passive"))
      (node (ref "CAP2") (pin "1") (pinfunction "1_1") (pintype "passive"))
      (node (ref "F2") (pin "1") (pinfunction "1_1") (pintype "passive"))
      (node (ref "F3") (pin "1") (pinfunction "1_1") (pintype "passive"))
      (node (ref "F4") (pin "1") (pinfunction "1_1") (pintype "passive"))
      (node (ref "F5") (pin "1") (pinfunction "1_1") (pintype "passive"))
      (node (ref "M2") (pin "5") (pinfunction "D_5") (pintype "passive"))
      (node (ref "M2") (pin "6") (pinfunction "D_6") (pintype "passive"))
      (node (ref "M2") (pin "7") (pinfunction "D_7") (pintype "passive"))
      (node (ref "M2") (pin "8") (pinfunction "D_8") (pintype "passive"))
      (node (ref "M2") (pin "9") (pinfunction "D_9") (pintype "passive"))
      (node (ref "R6") (pin "2") (pinfunction "2_2") (pintype "passive"))
    )
    (net (code "8") (name "Net-(C16-Pad1)") (class "Default")
      (node (ref "C16") (pin "1") (pinfunction "1_1") (pintype "passive"))
      (node (ref "CAP11") (pin "1") (pinfunction "1_1") (pintype "passive"))
      (node (ref "CAP15") (pin "1") (pinfunction "1_1") (pintype "passive"))
      (node (ref "CN1") (pin "1") (pinfunction "1_1") (pintype "passive"))
      (node (ref "L2") (pin "2") (pinfunction "2_2") (pintype "passive"))
      (node (ref "POTANT1") (pin "1") (pinfunction "1_1") (pintype "passive"))
      (node (ref "TVS2") (pin "1") (pinfunction "1_1") (pintype "passive"))
    )
    (net (code "9") (name "Net-(C17-Pad2)") (class "Default")
      (node (ref "C17") (pin "2") (pinfunction "2_2") (pintype "passive"))
      (node (ref "CAP12") (pin "1") (pinfunction "1_1") (pintype "passive"))
      (node (ref "CAP16") (pin "1") (pinfunction "1_1") (pintype "passive"))
      (node (ref "CN2") (pin "1") (pinfunction "1_1") (pintype "passive"))
      (node (ref "L3") (pin "2") (pinfunction "2_2") (pintype "passive"))
      (node (ref "POTANT2") (pin "1") (pinfunction "1_1") (pintype "passive"))
      (node (ref "TVS3") (pin "1") (pinfunction "1_1") (pintype "passive"))
    )
    (net (code "10") (name "Net-(C18-Pad1)") (class "Default")
      (node (ref "C18") (pin "1") (pinfunction "1_1") (pintype "passive"))
      (node (ref "CAP13") (pin "1") (pinfunction "1_1") (pintype "passive"))
      (node (ref "CAP17") (pin "1") (pinfunction "1_1") (pintype "passive"))
      (node (ref "CN3") (pin "1") (pinfunction "1_1") (pintype "passive"))
      (node (ref "L4") (pin "2") (pinfunction "2_2") (pintype "passive"))
      (node (ref "POTANT3") (pin "1") (pinfunction "1_1") (pintype "passive"))
      (node (ref "TVS4") (pin "1") (pinfunction "1_1") (pintype "passive"))
    )
    (net (code "11") (name "Net-(C19-Pad1)") (class "Default")
      (node (ref "C19") (pin "1") (pinfunction "1_1") (pintype "passive"))
      (node (ref "CAP14") (pin "1") (pinfunction "1_1") (pintype "passive"))
      (node (ref "CAP18") (pin "1") (pinfunction "1_1") (pintype "passive"))
      (node (ref "CN4") (pin "1") (pinfunction "1_1") (pintype "passive"))
      (node (ref "L5") (pin "2") (pinfunction "2_2") (pintype "passive"))
      (node (ref "POTANT4") (pin "1") (pinfunction "1_1") (pintype "passive"))
      (node (ref "TVS5") (pin "1") (pinfunction "1_1") (pintype "passive"))
    )
    (net (code "12") (name "Net-(DC4-Pad2)") (class "Default")
      (node (ref "DC4") (pin "2") (pinfunction "2_2") (pintype "passive"))
      (node (ref "DR6") (pin "1") (pinfunction "1_1") (pintype "passive"))
    )
    (net (code "13") (name "Net-(DD1-C)") (class "Default")
      (node (ref "DC1") (pin "2") (pinfunction "2_2") (pintype "passive"))
      (node (ref "DD1") (pin "1") (pinfunction "C_1") (pintype "passive"))
      (node (ref "U0") (pin "11") (pinfunction "BOOT_11") (pintype "passive"))
    )
    (net (code "14") (name "Net-(L1-Pad1)") (class "Default")
      (node (ref "L1") (pin "1") (pinfunction "1_1") (pintype "passive"))
      (node (ref "R1") (pin "2") (pinfunction "2_2") (pintype "passive"))
      (node (ref "R2") (pin "2") (pinfunction "2_2") (pintype "passive"))
      (node (ref "R4") (pin "2") (pinfunction "2_2") (pintype "passive"))
    )
    (net (code "15") (name "Net-(M1-G)") (class "Default")
      (node (ref "DR7") (pin "2") (pinfunction "2_2") (pintype "passive"))
      (node (ref "M1") (pin "4") (pinfunction "G_4") (pintype "passive"))
    )
    (net (code "16") (name "Net-(M2-G)") (class "Default")
      (node (ref "M2") (pin "4") (pinfunction "G_4") (pintype "passive"))
      (node (ref "U0") (pin "13") (pinfunction "HDRV_13") (pintype "passive"))
    )
    (net (code "17") (name "Net-(TVS1-C)") (class "Default")
      (node (ref "F1") (pin "1") (pinfunction "1_1") (pintype "passive"))
      (node (ref "TVS1") (pin "1") (pinfunction "C_1") (pintype "passive"))
      (node (ref "U23") (pin "1") (pinfunction "1_1") (pintype "passive"))
      (node (ref "U23") (pin "4") (pinfunction "4_4") (pintype "passive"))
    )
    (net (code "18") (name "Net-(U0-COMP)") (class "Default")
      (node (ref "DC3") (pin "2") (pinfunction "2_2") (pintype "passive"))
      (node (ref "DR6") (pin "2") (pinfunction "2_2") (pintype "passive"))
      (node (ref "U0") (pin "3") (pinfunction "COMP_3") (pintype "passive"))
    )
    (net (code "19") (name "Net-(U0-EN)") (class "Default")
      (node (ref "DR2") (pin "1") (pinfunction "1_1") (pintype "passive"))
      (node (ref "DR3") (pin "2") (pinfunction "2_2") (pintype "passive"))
      (node (ref "U0") (pin "15") (pinfunction "EN_15") (pintype "passive"))
    )
    (net (code "20") (name "Net-(U0-LDRV)") (class "Default")
      (node (ref "DR7") (pin "1") (pinfunction "1_1") (pintype "passive"))
      (node (ref "U0") (pin "8") (pinfunction "LDRV_8") (pintype "passive"))
    )
    (net (code "21") (name "Net-(U0-PGOOD)") (class "Default")
      (node (ref "DR1") (pin "1") (pinfunction "1_1") (pintype "passive"))
      (node (ref "U0") (pin "14") (pinfunction "PGOOD_14") (pintype "passive"))
    )
    (net (code "22") (name "Net-(U0-RT{slash}CLK)") (class "Default")
      (node (ref "DR4") (pin "1") (pinfunction "1_1") (pintype "passive"))
      (node (ref "U0") (pin "1") (pinfunction "RT/CLK_1") (pintype "passive"))
    )
    (net (code "23") (name "Net-(U0-SS{slash}TR)") (class "Default")
      (node (ref "DC2") (pin "2") (pinfunction "2_2") (pintype "passive"))
      (node (ref "U0") (pin "2") (pinfunction "SS/TR_2") (pintype "passive"))
    )
    (net (code "24") (name "Net-(U0-SW)") (class "Default")
      (node (ref "DC1") (pin "1") (pinfunction "1_1") (pintype "passive"))
      (node (ref "L1") (pin "2") (pinfunction "2_2") (pintype "passive"))
      (node (ref "M1") (pin "5") (pinfunction "D_5") (pintype "passive"))
      (node (ref "M1") (pin "6") (pinfunction "D_6") (pintype "passive"))
      (node (ref "M1") (pin "7") (pinfunction "D_7") (pintype "passive"))
      (node (ref "M1") (pin "8") (pinfunction "D_8") (pintype "passive"))
      (node (ref "M1") (pin "9") (pinfunction "D_9") (pintype "passive"))
      (node (ref "M2") (pin "1") (pinfunction "S_1") (pintype "passive"))
      (node (ref "M2") (pin "2") (pinfunction "S_2") (pintype "passive"))
      (node (ref "M2") (pin "3") (pinfunction "S_3") (pintype "passive"))
      (node (ref "R5") (pin "2") (pinfunction "2_2") (pintype "passive"))
      (node (ref "U0") (pin "12") (pinfunction "SW_12") (pintype "passive"))
    )
    (net (code "25") (name "Net-(U0-VCC)") (class "Default")
      (node (ref "DR5") (pin "1") (pinfunction "1_1") (pintype "passive"))
      (node (ref "U0") (pin "10") (pinfunction "VCC_10") (pintype "passive"))
    )
    (net (code "26") (name "Net-(U1-FB)") (class "Default")
      (node (ref "POTANT1") (pin "2") (pinfunction "2_2") (pintype "passive"))
      (node (ref "POTANT1") (pin "3") (pinfunction "3_3") (pintype "passive"))
      (node (ref "R8") (pin "1") (pinfunction "1_1") (pintype "passive"))
      (node (ref "U1") (pin "2") (pinfunction "FB_2") (pintype "passive"))
    )
    (net (code "27") (name "Net-(U1-SW)") (class "Default")
      (node (ref "L2") (pin "1") (pinfunction "1_1") (pintype "passive"))
      (node (ref "S1") (pin "2") (pinfunction "2_2") (pintype "passive"))
      (node (ref "U1") (pin "3") (pinfunction "SW_3") (pintype "passive"))
    )
    (net (code "28") (name "Net-(U1-VC)") (class "Default")
      (node (ref "C12") (pin "1") (pinfunction "1_1") (pintype "passive"))
      (node (ref "U1") (pin "4") (pinfunction "VC_4") (pintype "passive"))
    )
    (net (code "29") (name "Net-(U1-VIN)") (class "Default")
      (node (ref "C12") (pin "2") (pinfunction "2_2") (pintype "passive"))
      (node (ref "C8") (pin "1") (pinfunction "1_1") (pintype "passive"))
      (node (ref "CAP3") (pin "1") (pinfunction "1_1") (pintype "passive"))
      (node (ref "CAP7") (pin "1") (pinfunction "1_1") (pintype "passive"))
      (node (ref "F2") (pin "2") (pinfunction "2_2") (pintype "passive"))
      (node (ref "U1") (pin "5") (pinfunction "VIN_5") (pintype "passive"))
    )
    (net (code "30") (name "Net-(U2-FB)") (class "Default")
      (node (ref "POTANT2") (pin "2") (pinfunction "2_2") (pintype "passive"))
      (node (ref "POTANT2") (pin "3") (pinfunction "3_3") (pintype "passive"))
      (node (ref "R9") (pin "1") (pinfunction "1_1") (pintype "passive"))
      (node (ref "U2") (pin "2") (pinfunction "FB_2") (pintype "passive"))
    )
    (net (code "31") (name "Net-(U2-SW)") (class "Default")
      (node (ref "L3") (pin "1") (pinfunction "1_1") (pintype "passive"))
      (node (ref "S2") (pin "2") (pinfunction "2_2") (pintype "passive"))
      (node (ref "U2") (pin "3") (pinfunction "SW_3") (pintype "passive"))
    )
    (net (code "32") (name "Net-(U2-VC)") (class "Default")
      (node (ref "C13") (pin "1") (pinfunction "1_1") (pintype "passive"))
      (node (ref "U2") (pin "4") (pinfunction "VC_4") (pintype "passive"))
    )
    (net (code "33") (name "Net-(U2-VIN)") (class "Default")
      (node (ref "C13") (pin "2") (pinfunction "2_2") (pintype "passive"))
      (node (ref "C9") (pin "1") (pinfunction "1_1") (pintype "passive"))
      (node (ref "CAP4") (pin "1") (pinfunction "1_1") (pintype "passive"))
      (node (ref "CAP8") (pin "1") (pinfunction "1_1") (pintype "passive"))
      (node (ref "F3") (pin "2") (pinfunction "2_2") (pintype "passive"))
      (node (ref "U2") (pin "5") (pinfunction "VIN_5") (pintype "passive"))
    )
    (net (code "34") (name "Net-(U3-FB)") (class "Default")
      (node (ref "POTANT3") (pin "2") (pinfunction "2_2") (pintype "passive"))
      (node (ref "POTANT3") (pin "3") (pinfunction "3_3") (pintype "passive"))
      (node (ref "R10") (pin "1") (pinfunction "1_1") (pintype "passive"))
      (node (ref "U3") (pin "2") (pinfunction "FB_2") (pintype "passive"))
    )
    (net (code "35") (name "Net-(U3-SW)") (class "Default")
      (node (ref "L4") (pin "1") (pinfunction "1_1") (pintype "passive"))
      (node (ref "S3") (pin "2") (pinfunction "2_2") (pintype "passive"))
      (node (ref "U3") (pin "3") (pinfunction "SW_3") (pintype "passive"))
    )
    (net (code "36") (name "Net-(U3-VC)") (class "Default")
      (node (ref "C14") (pin "1") (pinfunction "1_1") (pintype "passive"))
      (node (ref "U3") (pin "4") (pinfunction "VC_4") (pintype "passive"))
    )
    (net (code "37") (name "Net-(U3-VIN)") (class "Default")
      (node (ref "C10") (pin "1") (pinfunction "1_1") (pintype "passive"))
      (node (ref "C14") (pin "2") (pinfunction "2_2") (pintype "passive"))
      (node (ref "CAP5") (pin "1") (pinfunction "1_1") (pintype "passive"))
      (node (ref "CAP9") (pin "1") (pinfunction "1_1") (pintype "passive"))
      (node (ref "F4") (pin "2") (pinfunction "2_2") (pintype "passive"))
      (node (ref "U3") (pin "5") (pinfunction "VIN_5") (pintype "passive"))
    )
    (net (code "38") (name "Net-(U4-FB)") (class "Default")
      (node (ref "POTANT4") (pin "2") (pinfunction "2_2") (pintype "passive"))
      (node (ref "POTANT4") (pin "3") (pinfunction "3_3") (pintype "passive"))
      (node (ref "R11") (pin "1") (pinfunction "1_1") (pintype "passive"))
      (node (ref "U4") (pin "2") (pinfunction "FB_2") (pintype "passive"))
    )
    (net (code "39") (name "Net-(U4-SW)") (class "Default")
      (node (ref "L5") (pin "1") (pinfunction "1_1") (pintype "passive"))
      (node (ref "S4") (pin "2") (pinfunction "2_2") (pintype "passive"))
      (node (ref "U4") (pin "3") (pinfunction "SW_3") (pintype "passive"))
    )
    (net (code "40") (name "Net-(U4-VC)") (class "Default")
      (node (ref "C15") (pin "2") (pinfunction "2_2") (pintype "passive"))
      (node (ref "U4") (pin "4") (pinfunction "VC_4") (pintype "passive"))
    )
    (net (code "41") (name "Net-(U4-VIN)") (class "Default")
      (node (ref "C11") (pin "1") (pinfunction "1_1") (pintype "passive"))
      (node (ref "C15") (pin "1") (pinfunction "1_1") (pintype "passive"))
      (node (ref "CAP10") (pin "1") (pinfunction "1_1") (pintype "passive"))
      (node (ref "CAP6") (pin "1") (pinfunction "1_1") (pintype "passive"))
      (node (ref "F5") (pin "2") (pinfunction "2_2") (pintype "passive"))
      (node (ref "U4") (pin "5") (pinfunction "VIN_5") (pintype "passive"))
    )
    (net (code "42") (name "VCC") (class "Default")
      (node (ref "DD1") (pin "2") (pinfunction "A_2") (pintype "passive"))
      (node (ref "DR1") (pin "2") (pinfunction "2_2") (pintype "passive"))
      (node (ref "DR5") (pin "2") (pinfunction "2_2") (pintype "passive"))
    )
  )
)
